# Robot_Car.net
KiCad netlist of a schematic drawn in EAGLE
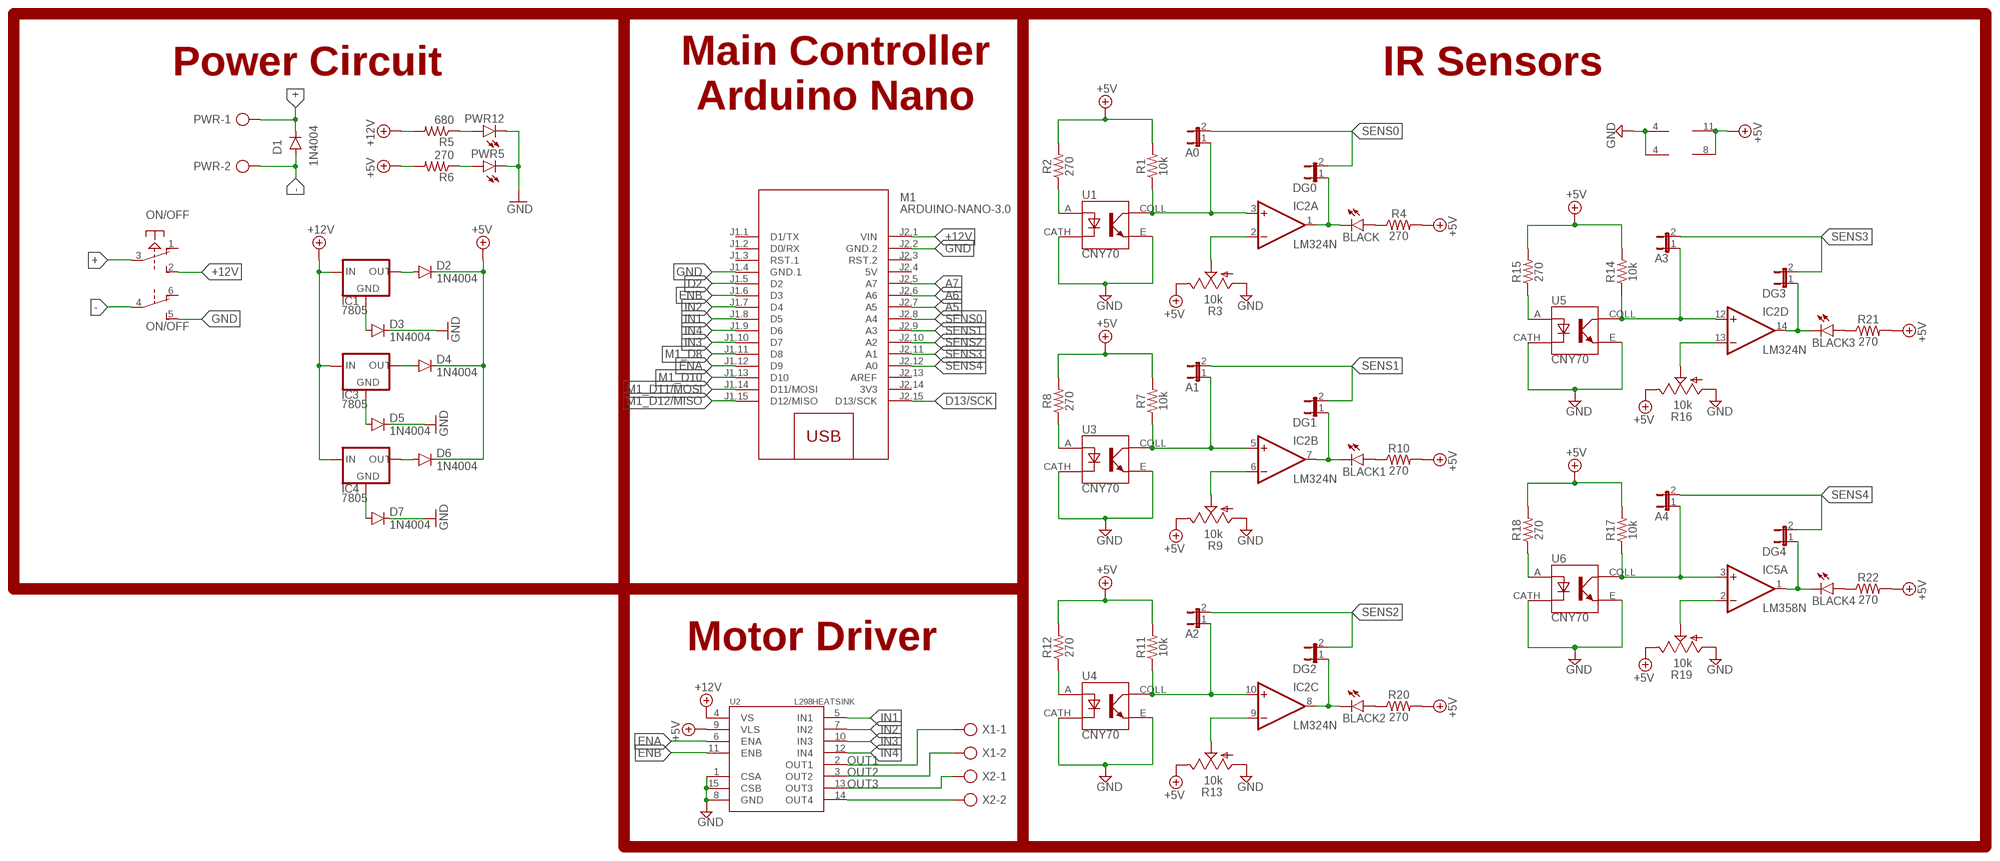
[diagram p0: schematic, sheet 1]

(export (version "E")
  (design (tool "Eeschema 10.0.6"))
  (components
    (comp (ref "A0")
      (value "JP1E")
      (footprint "eagle-import:JP1")
      (libsource (lib "eagle-import") (part "JP1E"))
    )
    (comp (ref "A1")
      (value "JP1E")
      (footprint "eagle-import:JP1")
      (libsource (lib "eagle-import") (part "JP1E"))
    )
    (comp (ref "A2")
      (value "JP1E")
      (footprint "eagle-import:JP1")
      (libsource (lib "eagle-import") (part "JP1E"))
    )
    (comp (ref "A3")
      (value "JP1E")
      (footprint "eagle-import:JP1")
      (libsource (lib "eagle-import") (part "JP1E"))
    )
    (comp (ref "A4")
      (value "JP1E")
      (footprint "eagle-import:JP1")
      (libsource (lib "eagle-import") (part "JP1E"))
    )
    (comp (ref "BLACK")
      (value "LED3MM")
      (footprint "eagle-import:LED3MM")
      (libsource (lib "eagle-import") (part "LED3MM"))
    )
    (comp (ref "BLACK1")
      (value "LED3MM")
      (footprint "eagle-import:LED3MM")
      (libsource (lib "eagle-import") (part "LED3MM"))
    )
    (comp (ref "BLACK2")
      (value "LED3MM")
      (footprint "eagle-import:LED3MM")
      (libsource (lib "eagle-import") (part "LED3MM"))
    )
    (comp (ref "BLACK3")
      (value "LED3MM")
      (footprint "eagle-import:LED3MM")
      (libsource (lib "eagle-import") (part "LED3MM"))
    )
    (comp (ref "BLACK4")
      (value "LED3MM")
      (footprint "eagle-import:LED3MM")
      (libsource (lib "eagle-import") (part "LED3MM"))
    )
    (comp (ref "D1")
      (value "1N4004")
      (footprint "eagle-import:DO41-10")
      (libsource (lib "eagle-import") (part "1N4004"))
    )
    (comp (ref "D2")
      (value "1N4004")
      (footprint "eagle-import:DO41-10")
      (libsource (lib "eagle-import") (part "1N4004"))
    )
    (comp (ref "D3")
      (value "1N4004")
      (footprint "eagle-import:DO41-10")
      (libsource (lib "eagle-import") (part "1N4004"))
    )
    (comp (ref "D4")
      (value "1N4004")
      (footprint "eagle-import:DO41-10")
      (libsource (lib "eagle-import") (part "1N4004"))
    )
    (comp (ref "D5")
      (value "1N4004")
      (footprint "eagle-import:DO41-10")
      (libsource (lib "eagle-import") (part "1N4004"))
    )
    (comp (ref "D6")
      (value "1N4004")
      (footprint "eagle-import:DO41-10")
      (libsource (lib "eagle-import") (part "1N4004"))
    )
    (comp (ref "D7")
      (value "1N4004")
      (footprint "eagle-import:DO41-10")
      (libsource (lib "eagle-import") (part "1N4004"))
    )
    (comp (ref "DG0")
      (value "JP1E")
      (footprint "eagle-import:JP1")
      (libsource (lib "eagle-import") (part "JP1E"))
    )
    (comp (ref "DG1")
      (value "JP1E")
      (footprint "eagle-import:JP1")
      (libsource (lib "eagle-import") (part "JP1E"))
    )
    (comp (ref "DG2")
      (value "JP1E")
      (footprint "eagle-import:JP1")
      (libsource (lib "eagle-import") (part "JP1E"))
    )
    (comp (ref "DG3")
      (value "JP1E")
      (footprint "eagle-import:JP1")
      (libsource (lib "eagle-import") (part "JP1E"))
    )
    (comp (ref "DG4")
      (value "JP1E")
      (footprint "eagle-import:JP1")
      (libsource (lib "eagle-import") (part "JP1E"))
    )
    (comp (ref "IC1")
      (value "7805")
      (footprint "eagle-import:78XXS")
      (libsource (lib "eagle-import") (part "78XXS"))
    )
    (comp (ref "IC2")
      (value "LM324N")
      (footprint "eagle-import:DIL14")
      (libsource (lib "eagle-import") (part "LM324N"))
    )
    (comp (ref "IC3")
      (value "7805")
      (footprint "eagle-import:78XXS")
      (libsource (lib "eagle-import") (part "78XXS"))
    )
    (comp (ref "IC4")
      (value "7805")
      (footprint "eagle-import:78XXS")
      (libsource (lib "eagle-import") (part "78XXS"))
    )
    (comp (ref "IC5")
      (value "LM358N")
      (footprint "eagle-import:DIL08")
      (libsource (lib "eagle-import") (part "LM358N"))
    )
    (comp (ref "M1")
      (value "ARDUINO-NANO-3.0")
      (footprint "eagle-import:ARDUINO-NANO-3.0")
      (libsource (lib "eagle-import") (part "ARDUINO-NANO-3.0"))
    )
    (comp (ref "ON/OFF")
      (value "PVA2R")
      (footprint "eagle-import:PVA2R")
      (libsource (lib "eagle-import") (part "PVA2R"))
    )
    (comp (ref "PWR")
      (value "AK500/2-H")
      (footprint "eagle-import:AK500_2-H")
      (libsource (lib "eagle-import") (part "AK500/2-H"))
    )
    (comp (ref "PWR5")
      (value "LED3MM")
      (footprint "eagle-import:LED3MM")
      (libsource (lib "eagle-import") (part "LED3MM"))
    )
    (comp (ref "PWR12")
      (value "LED3MM")
      (footprint "eagle-import:LED3MM")
      (libsource (lib "eagle-import") (part "LED3MM"))
    )
    (comp (ref "R1")
      (value "10k")
      (footprint "eagle-import:AXIAL-0.3")
      (libsource (lib "eagle-import") (part "RESISTORAXIAL-0.3"))
    )
    (comp (ref "R2")
      (value "270")
      (footprint "eagle-import:AXIAL-0.3")
      (libsource (lib "eagle-import") (part "RESISTORAXIAL-0.3"))
    )
    (comp (ref "R3")
      (value "10k")
      (footprint "eagle-import:CA6V")
      (libsource (lib "eagle-import") (part "TRIM_US-CA6V"))
    )
    (comp (ref "R4")
      (value "270")
      (footprint "eagle-import:AXIAL-0.3")
      (libsource (lib "eagle-import") (part "RESISTORAXIAL-0.3"))
    )
    (comp (ref "R5")
      (value "680")
      (footprint "eagle-import:AXIAL-0.3")
      (libsource (lib "eagle-import") (part "RESISTORAXIAL-0.3"))
    )
    (comp (ref "R6")
      (value "270")
      (footprint "eagle-import:AXIAL-0.3")
      (libsource (lib "eagle-import") (part "RESISTORAXIAL-0.3"))
    )
    (comp (ref "R7")
      (value "10k")
      (footprint "eagle-import:AXIAL-0.3")
      (libsource (lib "eagle-import") (part "RESISTORAXIAL-0.3"))
    )
    (comp (ref "R8")
      (value "270")
      (footprint "eagle-import:AXIAL-0.3")
      (libsource (lib "eagle-import") (part "RESISTORAXIAL-0.3"))
    )
    (comp (ref "R9")
      (value "10k")
      (footprint "eagle-import:CA6V")
      (libsource (lib "eagle-import") (part "TRIM_US-CA6V"))
    )
    (comp (ref "R10")
      (value "270")
      (footprint "eagle-import:AXIAL-0.3")
      (libsource (lib "eagle-import") (part "RESISTORAXIAL-0.3"))
    )
    (comp (ref "R11")
      (value "10k")
      (footprint "eagle-import:AXIAL-0.3")
      (libsource (lib "eagle-import") (part "RESISTORAXIAL-0.3"))
    )
    (comp (ref "R12")
      (value "270")
      (footprint "eagle-import:AXIAL-0.3")
      (libsource (lib "eagle-import") (part "RESISTORAXIAL-0.3"))
    )
    (comp (ref "R13")
      (value "10k")
      (footprint "eagle-import:CA6V")
      (libsource (lib "eagle-import") (part "TRIM_US-CA6V"))
    )
    (comp (ref "R14")
      (value "10k")
      (footprint "eagle-import:AXIAL-0.3")
      (libsource (lib "eagle-import") (part "RESISTORAXIAL-0.3"))
    )
    (comp (ref "R15")
      (value "270")
      (footprint "eagle-import:AXIAL-0.3")
      (libsource (lib "eagle-import") (part "RESISTORAXIAL-0.3"))
    )
    (comp (ref "R16")
      (value "10k")
      (footprint "eagle-import:CA6V")
      (libsource (lib "eagle-import") (part "TRIM_US-CA6V"))
    )
    (comp (ref "R17")
      (value "10k")
      (footprint "eagle-import:AXIAL-0.3")
      (libsource (lib "eagle-import") (part "RESISTORAXIAL-0.3"))
    )
    (comp (ref "R18")
      (value "270")
      (footprint "eagle-import:AXIAL-0.3")
      (libsource (lib "eagle-import") (part "RESISTORAXIAL-0.3"))
    )
    (comp (ref "R19")
      (value "10k")
      (footprint "eagle-import:CA6V")
      (libsource (lib "eagle-import") (part "TRIM_US-CA6V"))
    )
    (comp (ref "R20")
      (value "270")
      (footprint "eagle-import:AXIAL-0.3")
      (libsource (lib "eagle-import") (part "RESISTORAXIAL-0.3"))
    )
    (comp (ref "R21")
      (value "270")
      (footprint "eagle-import:AXIAL-0.3")
      (libsource (lib "eagle-import") (part "RESISTORAXIAL-0.3"))
    )
    (comp (ref "R22")
      (value "270")
      (footprint "eagle-import:AXIAL-0.3")
      (libsource (lib "eagle-import") (part "RESISTORAXIAL-0.3"))
    )
    (comp (ref "U1")
      (value "CNY70")
      (footprint "eagle-import:DIPS254W50P254L710H600Q4")
      (fields (field (name "MF") "Vishay"))
      (libsource (lib "eagle-import") (part "CNY70"))
    )
    (comp (ref "U2")
      (value "L298HEATSINK")
      (footprint "eagle-import:MULTIWATT15_6400BGHEATSINK")
      (libsource (lib "eagle-import") (part "L298HEATSINK"))
    )
    (comp (ref "U3")
      (value "CNY70")
      (footprint "eagle-import:DIPS254W50P254L710H600Q4")
      (fields (field (name "MF") "Vishay"))
      (libsource (lib "eagle-import") (part "CNY70"))
    )
    (comp (ref "U4")
      (value "CNY70")
      (footprint "eagle-import:DIPS254W50P254L710H600Q4")
      (fields (field (name "MF") "Vishay"))
      (libsource (lib "eagle-import") (part "CNY70"))
    )
    (comp (ref "U5")
      (value "CNY70")
      (footprint "eagle-import:DIPS254W50P254L710H600Q4")
      (fields (field (name "MF") "Vishay"))
      (libsource (lib "eagle-import") (part "CNY70"))
    )
    (comp (ref "U6")
      (value "CNY70")
      (footprint "eagle-import:DIPS254W50P254L710H600Q4")
      (fields (field (name "MF") "Vishay"))
      (libsource (lib "eagle-import") (part "CNY70"))
    )
    (comp (ref "X1")
      (value "AK500/2-H")
      (footprint "eagle-import:AK500_2-H")
      (libsource (lib "eagle-import") (part "AK500/2-H"))
    )
    (comp (ref "X2")
      (value "AK500/2-H")
      (footprint "eagle-import:AK500_2-H")
      (libsource (lib "eagle-import") (part "AK500/2-H"))
    )
  )
  (nets
    (net (code "1") (name "+") (class "Default")
      (node (ref "D1") (pin "C") (pinfunction "C_C") (pintype "passive"))
      (node (ref "ON/OFF") (pin "3") (pinfunction "P_3") (pintype "passive"))
      (node (ref "PWR") (pin "1") (pinfunction "KL_1") (pintype "passive"))
    )
    (net (code "2") (name "+5V") (class "Default")
      (node (ref "D2") (pin "C") (pinfunction "C_C") (pintype "passive"))
      (node (ref "D4") (pin "C") (pinfunction "C_C") (pintype "passive"))
      (node (ref "D6") (pin "C") (pinfunction "C_C") (pintype "passive"))
      (node (ref "IC2") (pin "11") (pinfunction "V-_11") (pintype "power_in"))
      (node (ref "IC5") (pin "8") (pinfunction "V+_8") (pintype "power_in"))
      (node (ref "R1") (pin "P$2") (pinfunction "2_P$2") (pintype "passive"))
      (node (ref "R10") (pin "P$2") (pinfunction "2_P$2") (pintype "passive"))
      (node (ref "R11") (pin "P$2") (pinfunction "2_P$2") (pintype "passive"))
      (node (ref "R12") (pin "P$2") (pinfunction "2_P$2") (pintype "passive"))
      (node (ref "R13") (pin "E") (pinfunction "E_E") (pintype "passive"))
      (node (ref "R14") (pin "P$2") (pinfunction "2_P$2") (pintype "passive"))
      (node (ref "R15") (pin "P$2") (pinfunction "2_P$2") (pintype "passive"))
      (node (ref "R16") (pin "E") (pinfunction "E_E") (pintype "passive"))
      (node (ref "R17") (pin "P$2") (pinfunction "2_P$2") (pintype "passive"))
      (node (ref "R18") (pin "P$2") (pinfunction "2_P$2") (pintype "passive"))
      (node (ref "R19") (pin "E") (pinfunction "E_E") (pintype "passive"))
      (node (ref "R2") (pin "P$2") (pinfunction "2_P$2") (pintype "passive"))
      (node (ref "R20") (pin "P$2") (pinfunction "2_P$2") (pintype "passive"))
      (node (ref "R21") (pin "P$2") (pinfunction "2_P$2") (pintype "passive"))
      (node (ref "R22") (pin "P$2") (pinfunction "2_P$2") (pintype "passive"))
      (node (ref "R3") (pin "E") (pinfunction "E_E") (pintype "passive"))
      (node (ref "R4") (pin "P$2") (pinfunction "2_P$2") (pintype "passive"))
      (node (ref "R6") (pin "P$2") (pinfunction "2_P$2") (pintype "passive"))
      (node (ref "R7") (pin "P$2") (pinfunction "2_P$2") (pintype "passive"))
      (node (ref "R8") (pin "P$2") (pinfunction "2_P$2") (pintype "passive"))
      (node (ref "R9") (pin "E") (pinfunction "E_E") (pintype "passive"))
      (node (ref "U2") (pin "9") (pinfunction "VLS_9") (pintype "bidirectional"))
    )
    (net (code "3") (name "+12V") (class "Default")
      (node (ref "IC1") (pin "IN") (pinfunction "IN_IN") (pintype "input"))
      (node (ref "IC3") (pin "IN") (pinfunction "IN_IN") (pintype "input"))
      (node (ref "IC4") (pin "IN") (pinfunction "IN_IN") (pintype "input"))
      (node (ref "M1") (pin "J2.1") (pinfunction "VIN_J2.1") (pintype "power_in"))
      (node (ref "ON/OFF") (pin "2") (pinfunction "S_2") (pintype "passive"))
      (node (ref "R5") (pin "P$2") (pinfunction "2_P$2") (pintype "passive"))
      (node (ref "U2") (pin "4") (pinfunction "VS_4") (pintype "bidirectional"))
    )
    (net (code "4") (name "-") (class "Default")
      (node (ref "D1") (pin "A") (pinfunction "A_A") (pintype "passive"))
      (node (ref "ON/OFF") (pin "4") (pinfunction "P_4") (pintype "passive"))
      (node (ref "PWR") (pin "2") (pinfunction "KL_2") (pintype "passive"))
    )
    (net (code "5") (name "/3V3") (class "Default")
      (node (ref "M1") (pin "J2.14") (pinfunction "3V3_J2.14") (pintype "power_in"))
    )
    (net (code "6") (name "/5V") (class "Default")
      (node (ref "M1") (pin "J2.4") (pinfunction "5V_J2.4") (pintype "power_in"))
    )
    (net (code "7") (name "/OUT1") (class "Default")
      (node (ref "U2") (pin "2") (pinfunction "OUT1_2") (pintype "bidirectional"))
      (node (ref "X1") (pin "1") (pinfunction "KL_1") (pintype "passive"))
    )
    (net (code "8") (name "/OUT2") (class "Default")
      (node (ref "U2") (pin "3") (pinfunction "OUT2_3") (pintype "bidirectional"))
      (node (ref "X1") (pin "2") (pinfunction "KL_2") (pintype "passive"))
    )
    (net (code "9") (name "/OUT3") (class "Default")
      (node (ref "U2") (pin "13") (pinfunction "OUT3_13") (pintype "bidirectional"))
      (node (ref "X2") (pin "1") (pinfunction "KL_1") (pintype "passive"))
    )
    (net (code "10") (name "A5") (class "Default")
      (node (ref "M1") (pin "J2.7") (pinfunction "A5_J2.7") (pintype "bidirectional"))
    )
    (net (code "11") (name "A6") (class "Default")
      (node (ref "M1") (pin "J2.6") (pinfunction "A6_J2.6") (pintype "bidirectional"))
    )
    (net (code "12") (name "A7") (class "Default")
      (node (ref "M1") (pin "J2.5") (pinfunction "A7_J2.5") (pintype "bidirectional"))
    )
    (net (code "13") (name "D2") (class "Default")
      (node (ref "M1") (pin "J1.5") (pinfunction "D2_J1.5") (pintype "bidirectional"))
    )
    (net (code "14") (name "D13{slash}SCK") (class "Default")
      (node (ref "M1") (pin "J2.15") (pinfunction "D13/SCK_J2.15") (pintype "bidirectional"))
    )
    (net (code "15") (name "ENA") (class "Default")
      (node (ref "M1") (pin "J1.12") (pinfunction "D9_J1.12") (pintype "bidirectional"))
      (node (ref "U2") (pin "6") (pinfunction "ENA_6") (pintype "bidirectional"))
    )
    (net (code "16") (name "ENB") (class "Default")
      (node (ref "M1") (pin "J1.6") (pinfunction "D3_J1.6") (pintype "bidirectional"))
      (node (ref "U2") (pin "11") (pinfunction "ENB_11") (pintype "bidirectional"))
    )
    (net (code "17") (name "GND") (class "Default")
      (node (ref "D3") (pin "C") (pinfunction "C_C") (pintype "passive"))
      (node (ref "D5") (pin "C") (pinfunction "C_C") (pintype "passive"))
      (node (ref "D7") (pin "C") (pinfunction "C_C") (pintype "passive"))
      (node (ref "IC2") (pin "4") (pinfunction "V+_4") (pintype "power_in"))
      (node (ref "IC5") (pin "4") (pinfunction "V-_4") (pintype "power_in"))
      (node (ref "M1") (pin "J1.4") (pinfunction "GND.1_J1.4") (pintype "power_in"))
      (node (ref "M1") (pin "J2.2") (pinfunction "GND.2_J2.2") (pintype "power_in"))
      (node (ref "ON/OFF") (pin "5") (pinfunction "S_5") (pintype "passive"))
      (node (ref "PWR12") (pin "K") (pinfunction "C_K") (pintype "passive"))
      (node (ref "PWR5") (pin "K") (pinfunction "C_K") (pintype "passive"))
      (node (ref "R13") (pin "A") (pinfunction "A_A") (pintype "passive"))
      (node (ref "R16") (pin "A") (pinfunction "A_A") (pintype "passive"))
      (node (ref "R19") (pin "A") (pinfunction "A_A") (pintype "passive"))
      (node (ref "R3") (pin "A") (pinfunction "A_A") (pintype "passive"))
      (node (ref "R9") (pin "A") (pinfunction "A_A") (pintype "passive"))
      (node (ref "U1") (pin "CATH") (pinfunction "CATH_CATH") (pintype "passive"))
      (node (ref "U1") (pin "E") (pinfunction "E_E") (pintype "passive"))
      (node (ref "U2") (pin "1") (pinfunction "CSA_1") (pintype "bidirectional"))
      (node (ref "U2") (pin "15") (pinfunction "CSB_15") (pintype "bidirectional"))
      (node (ref "U2") (pin "8") (pinfunction "GND_8") (pintype "bidirectional"))
      (node (ref "U3") (pin "CATH") (pinfunction "CATH_CATH") (pintype "passive"))
      (node (ref "U3") (pin "E") (pinfunction "E_E") (pintype "passive"))
      (node (ref "U4") (pin "CATH") (pinfunction "CATH_CATH") (pintype "passive"))
      (node (ref "U4") (pin "E") (pinfunction "E_E") (pintype "passive"))
      (node (ref "U5") (pin "CATH") (pinfunction "CATH_CATH") (pintype "passive"))
      (node (ref "U5") (pin "E") (pinfunction "E_E") (pintype "passive"))
      (node (ref "U6") (pin "CATH") (pinfunction "CATH_CATH") (pintype "passive"))
      (node (ref "U6") (pin "E") (pinfunction "E_E") (pintype "passive"))
    )
    (net (code "18") (name "IN1") (class "Default")
      (node (ref "M1") (pin "J1.8") (pinfunction "D5_J1.8") (pintype "bidirectional"))
      (node (ref "U2") (pin "5") (pinfunction "IN1_5") (pintype "bidirectional"))
    )
    (net (code "19") (name "IN2") (class "Default")
      (node (ref "M1") (pin "J1.7") (pinfunction "D4_J1.7") (pintype "bidirectional"))
      (node (ref "U2") (pin "7") (pinfunction "IN2_7") (pintype "bidirectional"))
    )
    (net (code "20") (name "IN3") (class "Default")
      (node (ref "M1") (pin "J1.10") (pinfunction "D7_J1.10") (pintype "bidirectional"))
      (node (ref "U2") (pin "10") (pinfunction "IN3_10") (pintype "bidirectional"))
    )
    (net (code "21") (name "IN4") (class "Default")
      (node (ref "M1") (pin "J1.9") (pinfunction "D6_J1.9") (pintype "bidirectional"))
      (node (ref "U2") (pin "12") (pinfunction "IN4_12") (pintype "bidirectional"))
    )
    (net (code "22") (name "M1_D8") (class "Default")
      (node (ref "M1") (pin "J1.11") (pinfunction "D8_J1.11") (pintype "bidirectional"))
    )
    (net (code "23") (name "M1_D10") (class "Default")
      (node (ref "M1") (pin "J1.13") (pinfunction "D10_J1.13") (pintype "bidirectional"))
    )
    (net (code "24") (name "M1_D11{slash}MOSI") (class "Default")
      (node (ref "M1") (pin "J1.14") (pinfunction "D11/MOSI_J1.14") (pintype "bidirectional"))
    )
    (net (code "25") (name "M1_D12{slash}MISO") (class "Default")
      (node (ref "M1") (pin "J1.15") (pinfunction "D12/MISO_J1.15") (pintype "bidirectional"))
    )
    (net (code "26") (name "Net-(BLACK-C)") (class "Default")
      (node (ref "BLACK") (pin "K") (pinfunction "C_K") (pintype "passive"))
      (node (ref "DG0") (pin "1") (pinfunction "1_1") (pintype "passive"))
      (node (ref "IC2") (pin "1") (pinfunction "OUT_1") (pintype "output"))
    )
    (net (code "27") (name "Net-(BLACK1-C)") (class "Default")
      (node (ref "BLACK1") (pin "K") (pinfunction "C_K") (pintype "passive"))
      (node (ref "DG1") (pin "1") (pinfunction "1_1") (pintype "passive"))
      (node (ref "IC2") (pin "7") (pinfunction "OUT_7") (pintype "output"))
    )
    (net (code "28") (name "Net-(BLACK2-C)") (class "Default")
      (node (ref "BLACK2") (pin "K") (pinfunction "C_K") (pintype "passive"))
      (node (ref "DG2") (pin "1") (pinfunction "1_1") (pintype "passive"))
      (node (ref "IC2") (pin "8") (pinfunction "OUT_8") (pintype "output"))
    )
    (net (code "29") (name "Net-(BLACK3-C)") (class "Default")
      (node (ref "BLACK3") (pin "K") (pinfunction "C_K") (pintype "passive"))
      (node (ref "DG3") (pin "1") (pinfunction "1_1") (pintype "passive"))
      (node (ref "IC2") (pin "14") (pinfunction "OUT_14") (pintype "output"))
    )
    (net (code "30") (name "Net-(BLACK4-C)") (class "Default")
      (node (ref "BLACK4") (pin "K") (pinfunction "C_K") (pintype "passive"))
      (node (ref "DG4") (pin "1") (pinfunction "1_1") (pintype "passive"))
      (node (ref "IC5") (pin "1") (pinfunction "OUT_1") (pintype "output"))
    )
    (net (code "31") (name "Net-(D2-PadA)") (class "Default")
      (node (ref "D2") (pin "A") (pinfunction "A_A") (pintype "passive"))
      (node (ref "IC1") (pin "OUT") (pinfunction "OUT_OUT") (pintype "passive"))
    )
    (net (code "32") (name "Net-(D3-PadA)") (class "Default")
      (node (ref "D3") (pin "A") (pinfunction "A_A") (pintype "passive"))
      (node (ref "IC1") (pin "GND") (pinfunction "GND_GND") (pintype "input"))
    )
    (net (code "33") (name "Net-(D4-PadA)") (class "Default")
      (node (ref "D4") (pin "A") (pinfunction "A_A") (pintype "passive"))
      (node (ref "IC3") (pin "OUT") (pinfunction "OUT_OUT") (pintype "passive"))
    )
    (net (code "34") (name "Net-(D5-PadA)") (class "Default")
      (node (ref "D5") (pin "A") (pinfunction "A_A") (pintype "passive"))
      (node (ref "IC3") (pin "GND") (pinfunction "GND_GND") (pintype "input"))
    )
    (net (code "35") (name "Net-(D6-PadA)") (class "Default")
      (node (ref "D6") (pin "A") (pinfunction "A_A") (pintype "passive"))
      (node (ref "IC4") (pin "OUT") (pinfunction "OUT_OUT") (pintype "passive"))
    )
    (net (code "36") (name "Net-(D7-PadA)") (class "Default")
      (node (ref "D7") (pin "A") (pinfunction "A_A") (pintype "passive"))
      (node (ref "IC4") (pin "GND") (pinfunction "GND_GND") (pintype "input"))
    )
    (net (code "37") (name "Net-(IC2A-+IN)") (class "Default")
      (node (ref "A0") (pin "1") (pinfunction "1_1") (pintype "passive"))
      (node (ref "IC2") (pin "3") (pinfunction "+IN_3") (pintype "input"))
      (node (ref "R1") (pin "P$1") (pinfunction "1_P$1") (pintype "passive"))
      (node (ref "U1") (pin "COLL") (pinfunction "COLL_COLL") (pintype "passive"))
    )
    (net (code "38") (name "Net-(IC2A--IN)") (class "Default")
      (node (ref "IC2") (pin "2") (pinfunction "-IN_2") (pintype "input"))
      (node (ref "R3") (pin "S") (pinfunction "S_S") (pintype "passive"))
    )
    (net (code "39") (name "Net-(IC2B-+IN)") (class "Default")
      (node (ref "A1") (pin "1") (pinfunction "1_1") (pintype "passive"))
      (node (ref "IC2") (pin "5") (pinfunction "+IN_5") (pintype "input"))
      (node (ref "R7") (pin "P$1") (pinfunction "1_P$1") (pintype "passive"))
      (node (ref "U3") (pin "COLL") (pinfunction "COLL_COLL") (pintype "passive"))
    )
    (net (code "40") (name "Net-(IC2B--IN)") (class "Default")
      (node (ref "IC2") (pin "6") (pinfunction "-IN_6") (pintype "input"))
      (node (ref "R9") (pin "S") (pinfunction "S_S") (pintype "passive"))
    )
    (net (code "41") (name "Net-(IC2C-+IN)") (class "Default")
      (node (ref "A2") (pin "1") (pinfunction "1_1") (pintype "passive"))
      (node (ref "IC2") (pin "10") (pinfunction "+IN_10") (pintype "input"))
      (node (ref "R11") (pin "P$1") (pinfunction "1_P$1") (pintype "passive"))
      (node (ref "U4") (pin "COLL") (pinfunction "COLL_COLL") (pintype "passive"))
    )
    (net (code "42") (name "Net-(IC2C--IN)") (class "Default")
      (node (ref "IC2") (pin "9") (pinfunction "-IN_9") (pintype "input"))
      (node (ref "R13") (pin "S") (pinfunction "S_S") (pintype "passive"))
    )
    (net (code "43") (name "Net-(IC2D-+IN)") (class "Default")
      (node (ref "A3") (pin "1") (pinfunction "1_1") (pintype "passive"))
      (node (ref "IC2") (pin "12") (pinfunction "+IN_12") (pintype "input"))
      (node (ref "R14") (pin "P$1") (pinfunction "1_P$1") (pintype "passive"))
      (node (ref "U5") (pin "COLL") (pinfunction "COLL_COLL") (pintype "passive"))
    )
    (net (code "44") (name "Net-(IC2D--IN)") (class "Default")
      (node (ref "IC2") (pin "13") (pinfunction "-IN_13") (pintype "input"))
      (node (ref "R16") (pin "S") (pinfunction "S_S") (pintype "passive"))
    )
    (net (code "45") (name "Net-(IC5A-+IN)") (class "Default")
      (node (ref "A4") (pin "1") (pinfunction "1_1") (pintype "passive"))
      (node (ref "IC5") (pin "3") (pinfunction "+IN_3") (pintype "input"))
      (node (ref "R17") (pin "P$1") (pinfunction "1_P$1") (pintype "passive"))
      (node (ref "U6") (pin "COLL") (pinfunction "COLL_COLL") (pintype "passive"))
    )
    (net (code "46") (name "Net-(IC5A--IN)") (class "Default")
      (node (ref "IC5") (pin "2") (pinfunction "-IN_2") (pintype "input"))
      (node (ref "R19") (pin "S") (pinfunction "S_S") (pintype "passive"))
    )
    (net (code "47") (name "Net-(R2-1)") (class "Default")
      (node (ref "R2") (pin "P$1") (pinfunction "1_P$1") (pintype "passive"))
      (node (ref "U1") (pin "A") (pinfunction "A_A") (pintype "passive"))
    )
    (net (code "48") (name "Net-(R4-1)") (class "Default")
      (node (ref "BLACK") (pin "A") (pinfunction "A_A") (pintype "passive"))
      (node (ref "R4") (pin "P$1") (pinfunction "1_P$1") (pintype "passive"))
    )
    (net (code "49") (name "Net-(R5-1)") (class "Default")
      (node (ref "PWR12") (pin "A") (pinfunction "A_A") (pintype "passive"))
      (node (ref "R5") (pin "P$1") (pinfunction "1_P$1") (pintype "passive"))
    )
    (net (code "50") (name "Net-(R6-1)") (class "Default")
      (node (ref "PWR5") (pin "A") (pinfunction "A_A") (pintype "passive"))
      (node (ref "R6") (pin "P$1") (pinfunction "1_P$1") (pintype "passive"))
    )
    (net (code "51") (name "Net-(R8-1)") (class "Default")
      (node (ref "R8") (pin "P$1") (pinfunction "1_P$1") (pintype "passive"))
      (node (ref "U3") (pin "A") (pinfunction "A_A") (pintype "passive"))
    )
    (net (code "52") (name "Net-(R10-1)") (class "Default")
      (node (ref "BLACK1") (pin "A") (pinfunction "A_A") (pintype "passive"))
      (node (ref "R10") (pin "P$1") (pinfunction "1_P$1") (pintype "passive"))
    )
    (net (code "53") (name "Net-(R12-1)") (class "Default")
      (node (ref "R12") (pin "P$1") (pinfunction "1_P$1") (pintype "passive"))
      (node (ref "U4") (pin "A") (pinfunction "A_A") (pintype "passive"))
    )
    (net (code "54") (name "Net-(R15-1)") (class "Default")
      (node (ref "R15") (pin "P$1") (pinfunction "1_P$1") (pintype "passive"))
      (node (ref "U5") (pin "A") (pinfunction "A_A") (pintype "passive"))
    )
    (net (code "55") (name "Net-(R18-1)") (class "Default")
      (node (ref "R18") (pin "P$1") (pinfunction "1_P$1") (pintype "passive"))
      (node (ref "U6") (pin "A") (pinfunction "A_A") (pintype "passive"))
    )
    (net (code "56") (name "Net-(R20-1)") (class "Default")
      (node (ref "BLACK2") (pin "A") (pinfunction "A_A") (pintype "passive"))
      (node (ref "R20") (pin "P$1") (pinfunction "1_P$1") (pintype "passive"))
    )
    (net (code "57") (name "Net-(R21-1)") (class "Default")
      (node (ref "BLACK3") (pin "A") (pinfunction "A_A") (pintype "passive"))
      (node (ref "R21") (pin "P$1") (pinfunction "1_P$1") (pintype "passive"))
    )
    (net (code "58") (name "Net-(R22-1)") (class "Default")
      (node (ref "BLACK4") (pin "A") (pinfunction "A_A") (pintype "passive"))
      (node (ref "R22") (pin "P$1") (pinfunction "1_P$1") (pintype "passive"))
    )
    (net (code "59") (name "Net-(U2-OUT4)") (class "Default")
      (node (ref "U2") (pin "14") (pinfunction "OUT4_14") (pintype "bidirectional"))
      (node (ref "X2") (pin "2") (pinfunction "KL_2") (pintype "passive"))
    )
    (net (code "60") (name "SENS0") (class "Default")
      (node (ref "A0") (pin "2") (pinfunction "2_2") (pintype "passive"))
      (node (ref "DG0") (pin "2") (pinfunction "2_2") (pintype "passive"))
      (node (ref "M1") (pin "J2.8") (pinfunction "A4_J2.8") (pintype "bidirectional"))
    )
    (net (code "61") (name "SENS1") (class "Default")
      (node (ref "A1") (pin "2") (pinfunction "2_2") (pintype "passive"))
      (node (ref "DG1") (pin "2") (pinfunction "2_2") (pintype "passive"))
      (node (ref "M1") (pin "J2.9") (pinfunction "A3_J2.9") (pintype "bidirectional"))
    )
    (net (code "62") (name "SENS2") (class "Default")
      (node (ref "A2") (pin "2") (pinfunction "2_2") (pintype "passive"))
      (node (ref "DG2") (pin "2") (pinfunction "2_2") (pintype "passive"))
      (node (ref "M1") (pin "J2.10") (pinfunction "A2_J2.10") (pintype "bidirectional"))
    )
    (net (code "63") (name "SENS3") (class "Default")
      (node (ref "A3") (pin "2") (pinfunction "2_2") (pintype "passive"))
      (node (ref "DG3") (pin "2") (pinfunction "2_2") (pintype "passive"))
      (node (ref "M1") (pin "J2.11") (pinfunction "A1_J2.11") (pintype "bidirectional"))
    )
    (net (code "64") (name "SENS4") (class "Default")
      (node (ref "A4") (pin "2") (pinfunction "2_2") (pintype "passive"))
      (node (ref "DG4") (pin "2") (pinfunction "2_2") (pintype "passive"))
      (node (ref "M1") (pin "J2.12") (pinfunction "A0_J2.12") (pintype "bidirectional"))
    )
    (net (code "65") (name "unconnected-(M1-AREF-PadJ2.13)") (class "Default")
      (node (ref "M1") (pin "J2.13") (pinfunction "AREF_J2.13") (pintype "bidirectional"))
    )
    (net (code "66") (name "unconnected-(M1-D0{slash}RX-PadJ1.2)") (class "Default")
      (node (ref "M1") (pin "J1.2") (pinfunction "D0/RX_J1.2") (pintype "bidirectional"))
    )
    (net (code "67") (name "unconnected-(M1-D1{slash}TX-PadJ1.1)") (class "Default")
      (node (ref "M1") (pin "J1.1") (pinfunction "D1/TX_J1.1") (pintype "bidirectional"))
    )
    (net (code "68") (name "unconnected-(M1-RST.1-PadJ1.3)") (class "Default")
      (node (ref "M1") (pin "J1.3") (pinfunction "RST.1_J1.3") (pintype "bidirectional"))
    )
    (net (code "69") (name "unconnected-(M1-RST.2-PadJ2.3)") (class "Default")
      (node (ref "M1") (pin "J2.3") (pinfunction "RST.2_J2.3") (pintype "bidirectional"))
    )
    (net (code "70") (name "unconnected-(ON/OFFA-O-Pad1)") (class "Default")
      (node (ref "ON/OFF") (pin "1") (pinfunction "O_1") (pintype "passive"))
    )
    (net (code "71") (name "unconnected-(ON/OFFB-O-Pad6)") (class "Default")
      (node (ref "ON/OFF") (pin "6") (pinfunction "O_6") (pintype "passive"))
    )
  )
)
